# ImageProc2_ver_24e.net
KiCad netlist of a schematic drawn in EAGLE
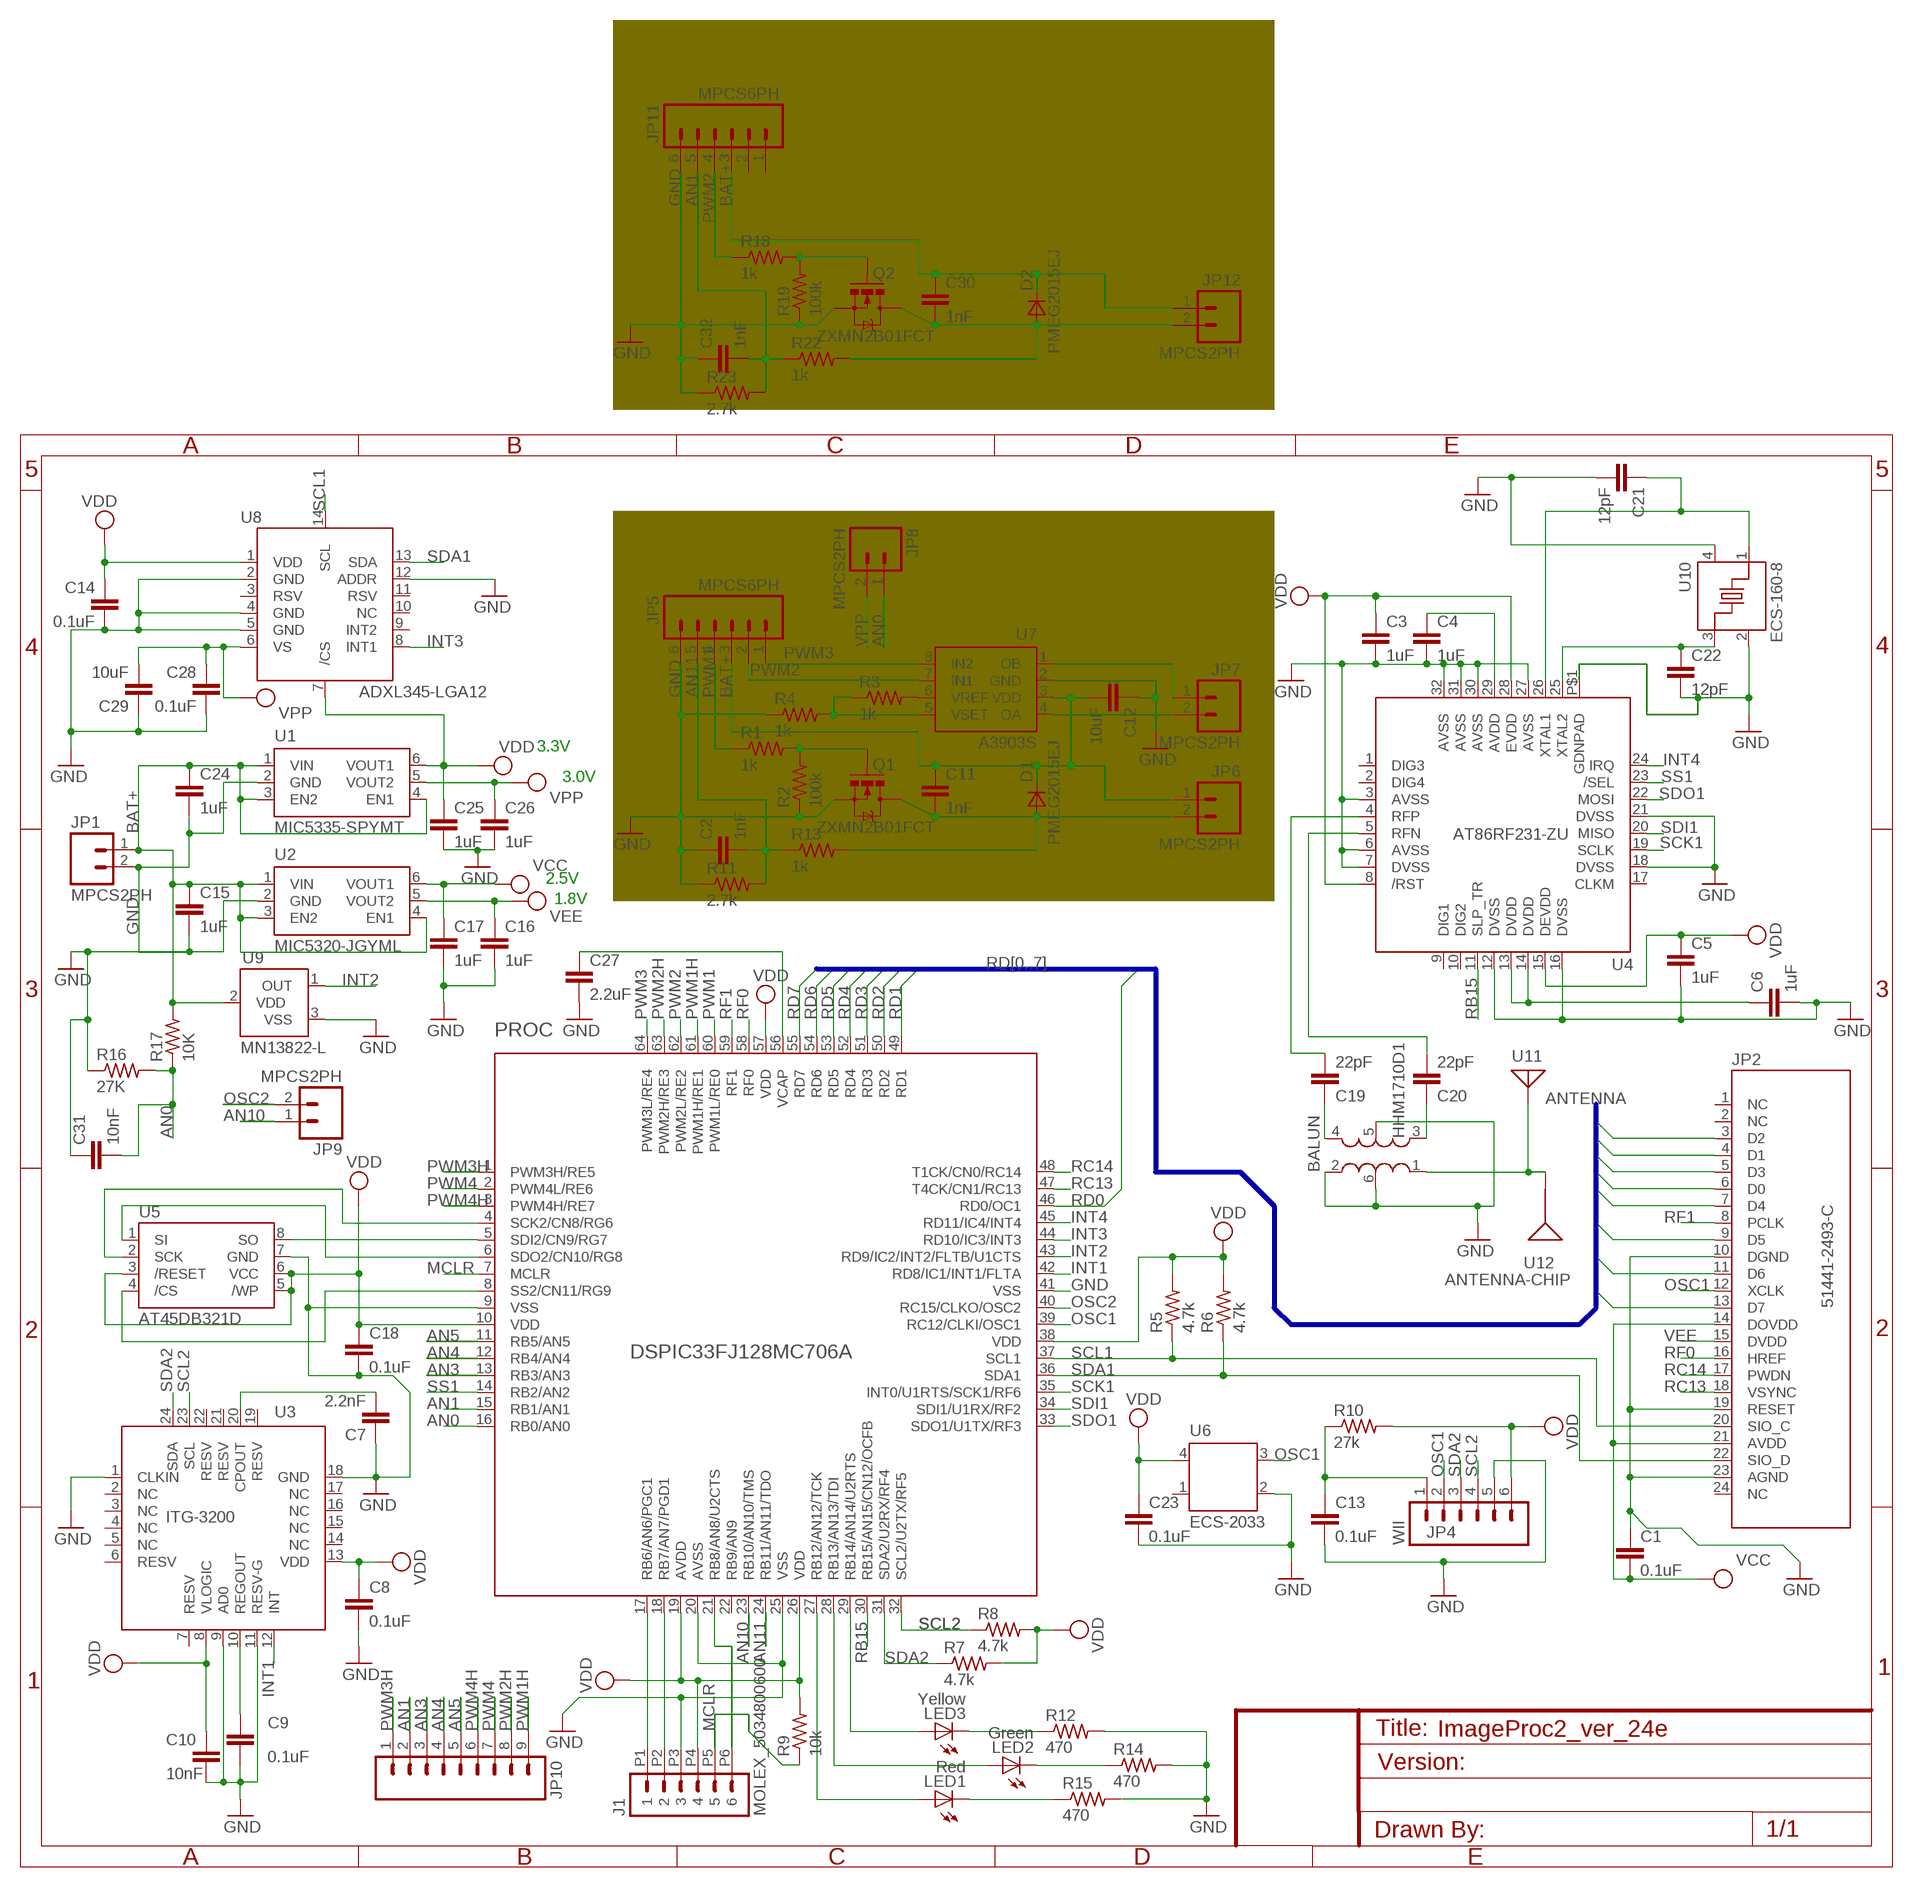
[diagram p0: schematic, sheet 1]

(export (version "E")
  (design (tool "Eeschema 10.0.6"))
  (components
    (comp (ref "BALUN")
      (value "HHM1710D1")
      (footprint "eagle-import:BALUN")
      (libsource (lib "eagle-import") (part "BALUNA"))
    )
    (comp (ref "C1")
      (value "0.1uF")
      (footprint "eagle-import:0402-CAP")
      (libsource (lib "eagle-import") (part "CAP0402-CAP"))
    )
    (comp (ref "C2")
      (value "1nF")
      (footprint "eagle-import:0402-CAP")
      (libsource (lib "eagle-import") (part "CAP0402-CAP"))
    )
    (comp (ref "C3")
      (value "1uF")
      (footprint "eagle-import:0402-CAP")
      (libsource (lib "eagle-import") (part "CAP0402-CAP"))
    )
    (comp (ref "C4")
      (value "1uF")
      (footprint "eagle-import:0402-CAP")
      (libsource (lib "eagle-import") (part "CAP0402-CAP"))
    )
    (comp (ref "C5")
      (value "1uF")
      (footprint "eagle-import:0402-CAP")
      (libsource (lib "eagle-import") (part "CAP0402-CAP"))
    )
    (comp (ref "C6")
      (value "1uF")
      (footprint "eagle-import:0402-CAP")
      (libsource (lib "eagle-import") (part "CAP0402-CAP"))
    )
    (comp (ref "C7")
      (value "2.2nF")
      (footprint "eagle-import:0402-CAP")
      (libsource (lib "eagle-import") (part "CAP0402-CAP"))
    )
    (comp (ref "C8")
      (value "0.1uF")
      (footprint "eagle-import:0402-CAP")
      (libsource (lib "eagle-import") (part "CAP0402-CAP"))
    )
    (comp (ref "C9")
      (value "0.1uF")
      (footprint "eagle-import:0402-CAP")
      (libsource (lib "eagle-import") (part "CAP0402-CAP"))
    )
    (comp (ref "C10")
      (value "10nF")
      (footprint "eagle-import:0402-CAP")
      (libsource (lib "eagle-import") (part "CAP0402-CAP"))
    )
    (comp (ref "C11")
      (value "1nF")
      (footprint "eagle-import:0402-CAP")
      (libsource (lib "eagle-import") (part "CAP0402-CAP"))
    )
    (comp (ref "C12")
      (value "10uF")
      (footprint "eagle-import:0603-CAP")
      (libsource (lib "eagle-import") (part "CAP0603-CAP"))
    )
    (comp (ref "C13")
      (value "0.1uF")
      (footprint "eagle-import:0402-CAP")
      (libsource (lib "eagle-import") (part "CAP0402-CAP"))
    )
    (comp (ref "C14")
      (value "0.1uF")
      (footprint "eagle-import:0402-CAP")
      (libsource (lib "eagle-import") (part "CAP0402-CAP"))
    )
    (comp (ref "C15")
      (value "1uF")
      (footprint "eagle-import:0402-CAP")
      (libsource (lib "eagle-import") (part "CAP0402-CAP"))
    )
    (comp (ref "C16")
      (value "1uF")
      (footprint "eagle-import:0402-CAP")
      (libsource (lib "eagle-import") (part "CAP0402-CAP"))
    )
    (comp (ref "C17")
      (value "1uF")
      (footprint "eagle-import:0402-CAP")
      (libsource (lib "eagle-import") (part "CAP0402-CAP"))
    )
    (comp (ref "C18")
      (value "0.1uF")
      (footprint "eagle-import:0402-CAP")
      (libsource (lib "eagle-import") (part "CAP0402-CAP"))
    )
    (comp (ref "C19")
      (value "22pF")
      (footprint "eagle-import:0402-CAP")
      (libsource (lib "eagle-import") (part "CAP0402-CAP"))
    )
    (comp (ref "C20")
      (value "22pF")
      (footprint "eagle-import:0402-CAP")
      (libsource (lib "eagle-import") (part "CAP0402-CAP"))
    )
    (comp (ref "C21")
      (value "12pF")
      (footprint "eagle-import:0402-CAP")
      (libsource (lib "eagle-import") (part "CAP0402-CAP"))
    )
    (comp (ref "C22")
      (value "12pF")
      (footprint "eagle-import:0402-CAP")
      (libsource (lib "eagle-import") (part "CAP0402-CAP"))
    )
    (comp (ref "C23")
      (value "0.1uF")
      (footprint "eagle-import:0402-CAP")
      (libsource (lib "eagle-import") (part "CAP0402-CAP"))
    )
    (comp (ref "C24")
      (value "1uF")
      (footprint "eagle-import:0402-CAP")
      (libsource (lib "eagle-import") (part "CAP0402-CAP"))
    )
    (comp (ref "C25")
      (value "1uF")
      (footprint "eagle-import:0402-CAP")
      (libsource (lib "eagle-import") (part "CAP0402-CAP"))
    )
    (comp (ref "C26")
      (value "1uF")
      (footprint "eagle-import:0402-CAP")
      (libsource (lib "eagle-import") (part "CAP0402-CAP"))
    )
    (comp (ref "C27")
      (value "2.2uF")
      (footprint "eagle-import:0402-CAP")
      (libsource (lib "eagle-import") (part "CAP0402-CAP"))
    )
    (comp (ref "C28")
      (value "0.1uF")
      (footprint "eagle-import:0402-CAP")
      (libsource (lib "eagle-import") (part "CAP0402-CAP"))
    )
    (comp (ref "C29")
      (value "10uF")
      (footprint "eagle-import:0603-CAP")
      (libsource (lib "eagle-import") (part "CAP0603-CAP"))
    )
    (comp (ref "C30")
      (value "1nF")
      (footprint "eagle-import:0402-CAP")
      (libsource (lib "eagle-import") (part "CAP0402-CAP"))
    )
    (comp (ref "C31")
      (value "10nF")
      (footprint "eagle-import:0402-CAP")
      (libsource (lib "eagle-import") (part "CAP0402-CAP"))
    )
    (comp (ref "C32")
      (value "1nF")
      (footprint "eagle-import:0402-CAP")
      (libsource (lib "eagle-import") (part "CAP0402-CAP"))
    )
    (comp (ref "D1")
      (value "PMEG2015EJ")
      (footprint "eagle-import:SOD323")
      (libsource (lib "eagle-import") (part "DSOD323"))
    )
    (comp (ref "D2")
      (value "PMEG2015EJ")
      (footprint "eagle-import:SOD323")
      (libsource (lib "eagle-import") (part "DSOD323"))
    )
    (comp (ref "J1")
      (value "MOLEX_5034800600")
      (footprint "eagle-import:MOLEX_5034800600")
      (libsource (lib "eagle-import") (part "MOLEX_5034800600"))
    )
    (comp (ref "JP1")
      (value "MPCS2PH")
      (footprint "eagle-import:MOLEX-PICO_CLASP_S2P")
      (libsource (lib "eagle-import") (part "MPCS2PH"))
    )
    (comp (ref "JP2")
      (value "51441-2493-C")
      (footprint "eagle-import:MOLEX-52740-2490")
      (libsource (lib "eagle-import") (part "OV7660FSL_CON-24"))
    )
    (comp (ref "JP4")
      (value "WII")
      (footprint "eagle-import:MOLEX-PICO_CLASP_S6P")
      (libsource (lib "eagle-import") (part "MPCS6PH"))
    )
    (comp (ref "JP5")
      (value "MPCS6PH")
      (footprint "eagle-import:MOLEX-PICO_CLASP_S6P")
      (libsource (lib "eagle-import") (part "MPCS6PH"))
    )
    (comp (ref "JP6")
      (value "MPCS2PH")
      (footprint "eagle-import:MOLEX-PICO_CLASP_S2P")
      (libsource (lib "eagle-import") (part "MPCS2PH"))
    )
    (comp (ref "JP7")
      (value "MPCS2PH")
      (footprint "eagle-import:MOLEX-PICO_CLASP_S2P")
      (libsource (lib "eagle-import") (part "MPCS2PH"))
    )
    (comp (ref "JP8")
      (value "MPCS2PH")
      (footprint "eagle-import:MOLEX-PICO_CLASP_S2P")
      (libsource (lib "eagle-import") (part "MPCS2PH"))
    )
    (comp (ref "JP9")
      (value "MPCS2PH")
      (footprint "eagle-import:MOLEX-PICO_CLASP_S2P")
      (libsource (lib "eagle-import") (part "MPCS2PH"))
    )
    (comp (ref "JP10")
      (value "SOLDER_PADS_9P")
      (footprint "eagle-import:SOLDER_PADS_9P")
      (libsource (lib "eagle-import") (part "SOLDER_PADS_9P"))
    )
    (comp (ref "JP11")
      (value "MPCS6PH")
      (footprint "eagle-import:MOLEX-PICO_CLASP_S6P")
      (libsource (lib "eagle-import") (part "MPCS6PH"))
    )
    (comp (ref "JP12")
      (value "MPCS2PH")
      (footprint "eagle-import:MOLEX-PICO_CLASP_S2P")
      (libsource (lib "eagle-import") (part "MPCS2PH"))
    )
    (comp (ref "LED1")
      (value "Red")
      (footprint "eagle-import:CHIP-LED0603")
      (libsource (lib "eagle-import") (part "LEDCHIP-LED0603"))
    )
    (comp (ref "LED2")
      (value "Green")
      (footprint "eagle-import:CHIP-LED0603")
      (libsource (lib "eagle-import") (part "LEDCHIP-LED0603"))
    )
    (comp (ref "LED3")
      (value "Yellow")
      (footprint "eagle-import:CHIP-LED0603")
      (libsource (lib "eagle-import") (part "LEDCHIP-LED0603"))
    )
    (comp (ref "PROC")
      (value "DSPIC33FJ128MC706A")
      (footprint "eagle-import:TQFP64")
      (libsource (lib "eagle-import") (part "DSPIC33FJ128MC706-I/PT"))
    )
    (comp (ref "Q1")
      (value "ZXMN2B01FCT")
      (footprint "eagle-import:SOT23-3")
      (libsource (lib "eagle-import") (part "MOSFET-NCHANNELSMD"))
    )
    (comp (ref "Q2")
      (value "ZXMN2B01FCT")
      (footprint "eagle-import:SOT23-3")
      (libsource (lib "eagle-import") (part "MOSFET-NCHANNELSMD"))
    )
    (comp (ref "R1")
      (value "1k")
      (footprint "eagle-import:R0402")
      (libsource (lib "eagle-import") (part "R-US_R0402"))
    )
    (comp (ref "R2")
      (value "100k")
      (footprint "eagle-import:R0402")
      (libsource (lib "eagle-import") (part "R-US_R0402"))
    )
    (comp (ref "R3")
      (value "1k")
      (footprint "eagle-import:R0402")
      (libsource (lib "eagle-import") (part "R-US_R0402"))
    )
    (comp (ref "R4")
      (value "1k")
      (footprint "eagle-import:R0402")
      (libsource (lib "eagle-import") (part "R-US_R0402"))
    )
    (comp (ref "R5")
      (value "4.7k")
      (footprint "eagle-import:R0402")
      (libsource (lib "eagle-import") (part "R-US_R0402"))
    )
    (comp (ref "R6")
      (value "4.7k")
      (footprint "eagle-import:R0402")
      (libsource (lib "eagle-import") (part "R-US_R0402"))
    )
    (comp (ref "R7")
      (value "4.7k")
      (footprint "eagle-import:R0402")
      (libsource (lib "eagle-import") (part "R-US_R0402"))
    )
    (comp (ref "R8")
      (value "4.7k")
      (footprint "eagle-import:R0402")
      (libsource (lib "eagle-import") (part "R-US_R0402"))
    )
    (comp (ref "R9")
      (value "10k")
      (footprint "eagle-import:R0402")
      (libsource (lib "eagle-import") (part "R-US_R0402"))
    )
    (comp (ref "R10")
      (value "27k")
      (footprint "eagle-import:R0402")
      (libsource (lib "eagle-import") (part "R-US_R0402"))
    )
    (comp (ref "R11")
      (value "2.7k")
      (footprint "eagle-import:R0402")
      (libsource (lib "eagle-import") (part "R-US_R0402"))
    )
    (comp (ref "R12")
      (value "470")
      (footprint "eagle-import:R0402")
      (libsource (lib "eagle-import") (part "R-US_R0402"))
    )
    (comp (ref "R13")
      (value "1k")
      (footprint "eagle-import:R0402")
      (libsource (lib "eagle-import") (part "R-US_R0402"))
    )
    (comp (ref "R14")
      (value "470")
      (footprint "eagle-import:R0402")
      (libsource (lib "eagle-import") (part "R-US_R0402"))
    )
    (comp (ref "R15")
      (value "470")
      (footprint "eagle-import:R0402")
      (libsource (lib "eagle-import") (part "R-US_R0402"))
    )
    (comp (ref "R16")
      (value "27K")
      (footprint "eagle-import:R0402")
      (libsource (lib "eagle-import") (part "R-US_R0402"))
    )
    (comp (ref "R17")
      (value "10K")
      (footprint "eagle-import:R0402")
      (libsource (lib "eagle-import") (part "R-US_R0402"))
    )
    (comp (ref "R18")
      (value "1k")
      (footprint "eagle-import:R0402")
      (libsource (lib "eagle-import") (part "R-US_R0402"))
    )
    (comp (ref "R19")
      (value "100k")
      (footprint "eagle-import:R0402")
      (libsource (lib "eagle-import") (part "R-US_R0402"))
    )
    (comp (ref "R22")
      (value "1k")
      (footprint "eagle-import:R0402")
      (libsource (lib "eagle-import") (part "R-US_R0402"))
    )
    (comp (ref "R23")
      (value "2.7k")
      (footprint "eagle-import:R0402")
      (libsource (lib "eagle-import") (part "R-US_R0402"))
    )
    (comp (ref "U1")
      (value "MIC5335-SPYMT")
      (footprint "eagle-import:MLF-6")
      (libsource (lib "eagle-import") (part "MIC5320-JGYML"))
    )
    (comp (ref "U2")
      (value "MIC5320-JGYML")
      (footprint "eagle-import:MLF-6")
      (libsource (lib "eagle-import") (part "MIC5320-JGYML"))
    )
    (comp (ref "U3")
      (value "ITG-3200")
      (footprint "eagle-import:QFN-24")
      (libsource (lib "eagle-import") (part "ITG-3200-00"))
    )
    (comp (ref "U4")
      (value "AT86RF231-ZU")
      (footprint "eagle-import:QFN-32")
      (libsource (lib "eagle-import") (part "AT86RF231-ZU"))
    )
    (comp (ref "U5")
      (value "AT45DB321D")
      (footprint "eagle-import:MLF(VDFN)-8")
      (libsource (lib "eagle-import") (part "AT45DB321D"))
    )
    (comp (ref "U6")
      (value "ECS-2033")
      (footprint "eagle-import:OSCILLATOR-SMD")
      (libsource (lib "eagle-import") (part "OSCILLATORS"))
    )
    (comp (ref "U7")
      (value "A3903S")
      (footprint "eagle-import:DFN-8")
      (libsource (lib "eagle-import") (part "A3903S"))
    )
    (comp (ref "U8")
      (value "ADXL345-LGA12")
      (footprint "eagle-import:LGA14")
      (libsource (lib "eagle-import") (part "ADXL345"))
    )
    (comp (ref "U9")
      (value "MN13822-L")
      (footprint "eagle-import:SOT-23-3")
      (libsource (lib "eagle-import") (part "VOL_DETECTOR"))
    )
    (comp (ref "U10")
      (value "ECS-160-8")
      (footprint "eagle-import:CRYSTAL-SMD")
      (libsource (lib "eagle-import") (part "CRYSTALS"))
    )
    (comp (ref "U11")
      (value "ANTENNA")
      (footprint "eagle-import:ANTENNA_PAD")
      (libsource (lib "eagle-import") (part "ANTENNA"))
    )
    (comp (ref "U12")
      (value "ANTENNA-CHIP")
      (footprint "eagle-import:ANTENNA-CHIP")
      (libsource (lib "eagle-import") (part "ANTENNA-CHIP"))
    )
  )
  (nets
    (net (code "1") (name "/AN0") (class "Default")
      (node (ref "C31") (pin "2") (pinfunction "2_2") (pintype "passive"))
      (node (ref "JP8") (pin "1") (pinfunction "1_1") (pintype "passive"))
      (node (ref "PROC") (pin "16") (pinfunction "RB0/AN0_16") (pintype "bidirectional"))
      (node (ref "R16") (pin "2") (pinfunction "2_2") (pintype "passive"))
      (node (ref "R17") (pin "1") (pinfunction "1_1") (pintype "passive"))
    )
    (net (code "2") (name "/AN1") (class "Default")
      (node (ref "C32") (pin "2") (pinfunction "2_2") (pintype "passive"))
      (node (ref "JP10") (pin "2") (pinfunction "2_2") (pintype "passive"))
      (node (ref "JP11") (pin "5") (pinfunction "5_5") (pintype "passive"))
      (node (ref "PROC") (pin "15") (pinfunction "RB1/AN1_15") (pintype "bidirectional"))
      (node (ref "R22") (pin "1") (pinfunction "1_1") (pintype "passive"))
      (node (ref "R23") (pin "2") (pinfunction "2_2") (pintype "passive"))
    )
    (net (code "3") (name "/AN3") (class "Default")
      (node (ref "JP10") (pin "3") (pinfunction "3_3") (pintype "passive"))
      (node (ref "PROC") (pin "13") (pinfunction "RB3/AN3_13") (pintype "bidirectional"))
    )
    (net (code "4") (name "/AN4") (class "Default")
      (node (ref "JP10") (pin "4") (pinfunction "4_4") (pintype "passive"))
      (node (ref "PROC") (pin "12") (pinfunction "RB4/AN4_12") (pintype "bidirectional"))
    )
    (net (code "5") (name "/AN5") (class "Default")
      (node (ref "JP10") (pin "5") (pinfunction "5_5") (pintype "passive"))
      (node (ref "PROC") (pin "11") (pinfunction "RB5/AN5_11") (pintype "bidirectional"))
    )
    (net (code "6") (name "/AN10") (class "Default")
      (node (ref "JP9") (pin "1") (pinfunction "1_1") (pintype "passive"))
      (node (ref "PROC") (pin "23") (pinfunction "RB10/AN10/TMS_23") (pintype "bidirectional"))
    )
    (net (code "7") (name "/AN11") (class "Default")
      (node (ref "C2") (pin "2") (pinfunction "2_2") (pintype "passive"))
      (node (ref "JP5") (pin "5") (pinfunction "5_5") (pintype "passive"))
      (node (ref "PROC") (pin "24") (pinfunction "RB11/AN11/TDO_24") (pintype "bidirectional"))
      (node (ref "R11") (pin "2") (pinfunction "2_2") (pintype "passive"))
      (node (ref "R13") (pin "1") (pinfunction "1_1") (pintype "passive"))
    )
    (net (code "8") (name "/BAT+") (class "Default")
      (node (ref "C11") (pin "1") (pinfunction "1_1") (pintype "passive"))
      (node (ref "C12") (pin "2") (pinfunction "2_2") (pintype "passive"))
      (node (ref "C15") (pin "1") (pinfunction "1_1") (pintype "passive"))
      (node (ref "C24") (pin "1") (pinfunction "1_1") (pintype "passive"))
      (node (ref "C30") (pin "1") (pinfunction "1_1") (pintype "passive"))
      (node (ref "D1") (pin "1") (pinfunction "C_1") (pintype "passive"))
      (node (ref "D2") (pin "1") (pinfunction "C_1") (pintype "passive"))
      (node (ref "JP1") (pin "1") (pinfunction "1_1") (pintype "passive"))
      (node (ref "JP11") (pin "3") (pinfunction "3_3") (pintype "passive"))
      (node (ref "JP12") (pin "1") (pinfunction "1_1") (pintype "passive"))
      (node (ref "JP5") (pin "3") (pinfunction "3_3") (pintype "passive"))
      (node (ref "JP6") (pin "1") (pinfunction "1_1") (pintype "passive"))
      (node (ref "R17") (pin "2") (pinfunction "2_2") (pintype "passive"))
      (node (ref "U1") (pin "1") (pinfunction "VIN_1") (pintype "bidirectional"))
      (node (ref "U1") (pin "3") (pinfunction "EN2_3") (pintype "bidirectional"))
      (node (ref "U1") (pin "4") (pinfunction "EN1_4") (pintype "bidirectional"))
      (node (ref "U2") (pin "1") (pinfunction "VIN_1") (pintype "bidirectional"))
      (node (ref "U2") (pin "3") (pinfunction "EN2_3") (pintype "bidirectional"))
      (node (ref "U2") (pin "4") (pinfunction "EN1_4") (pintype "bidirectional"))
      (node (ref "U7") (pin "3") (pinfunction "VDD_3") (pintype "bidirectional"))
      (node (ref "U9") (pin "2") (pinfunction "VDD_2") (pintype "bidirectional"))
    )
    (net (code "9") (name "/INT1") (class "Default")
      (node (ref "PROC") (pin "42") (pinfunction "RD8/IC1/INT1/FLTA_42") (pintype "bidirectional"))
      (node (ref "U3") (pin "12") (pinfunction "INT_12") (pintype "bidirectional"))
    )
    (net (code "10") (name "/INT2") (class "Default")
      (node (ref "PROC") (pin "43") (pinfunction "RD9/IC2/INT2/FLTB/U1CTS_43") (pintype "bidirectional"))
      (node (ref "U9") (pin "1") (pinfunction "OUT_1") (pintype "bidirectional"))
    )
    (net (code "11") (name "/INT3") (class "Default")
      (node (ref "PROC") (pin "44") (pinfunction "RD10/IC3/INT3_44") (pintype "bidirectional"))
      (node (ref "U8") (pin "8") (pinfunction "INT1_8") (pintype "bidirectional"))
    )
    (net (code "12") (name "/INT4") (class "Default")
      (node (ref "PROC") (pin "45") (pinfunction "RD11/IC4/INT4_45") (pintype "bidirectional"))
      (node (ref "U4") (pin "24") (pinfunction "IRQ_24") (pintype "bidirectional"))
    )
    (net (code "13") (name "/MCLR") (class "Default")
      (node (ref "J1") (pin "P5") (pinfunction "5_P5") (pintype "passive"))
      (node (ref "PROC") (pin "7") (pinfunction "MCLR_7") (pintype "input"))
      (node (ref "R9") (pin "1") (pinfunction "1_1") (pintype "passive"))
    )
    (net (code "14") (name "/OSC1") (class "Default")
      (node (ref "JP2") (pin "12") (pinfunction "XCLK_12") (pintype "bidirectional"))
      (node (ref "JP4") (pin "2") (pinfunction "2_2") (pintype "passive"))
      (node (ref "PROC") (pin "39") (pinfunction "RC12/CLKI/OSC1_39") (pintype "bidirectional"))
      (node (ref "U6") (pin "3") (pinfunction "OUT_3") (pintype "bidirectional"))
    )
    (net (code "15") (name "/OSC2") (class "Default")
      (node (ref "JP9") (pin "2") (pinfunction "2_2") (pintype "passive"))
      (node (ref "PROC") (pin "40") (pinfunction "RC15/CLKO/OSC2_40") (pintype "bidirectional"))
    )
    (net (code "16") (name "/PWM1") (class "Default")
      (node (ref "JP5") (pin "4") (pinfunction "4_4") (pintype "passive"))
      (node (ref "PROC") (pin "60") (pinfunction "PWM1L/RE0_60") (pintype "bidirectional"))
      (node (ref "R1") (pin "1") (pinfunction "1_1") (pintype "passive"))
    )
    (net (code "17") (name "/PWM1H") (class "Default")
      (node (ref "JP10") (pin "9") (pinfunction "9_9") (pintype "passive"))
      (node (ref "PROC") (pin "61") (pinfunction "PWM1H/RE1_61") (pintype "bidirectional"))
    )
    (net (code "18") (name "/PWM2") (class "Default")
      (node (ref "JP11") (pin "4") (pinfunction "4_4") (pintype "passive"))
      (node (ref "JP5") (pin "2") (pinfunction "2_2") (pintype "passive"))
      (node (ref "PROC") (pin "62") (pinfunction "PWM2L/RE2_62") (pintype "bidirectional"))
      (node (ref "R18") (pin "1") (pinfunction "1_1") (pintype "passive"))
      (node (ref "U7") (pin "7") (pinfunction "IN1_7") (pintype "bidirectional"))
    )
    (net (code "19") (name "/PWM2H") (class "Default")
      (node (ref "JP10") (pin "8") (pinfunction "8_8") (pintype "passive"))
      (node (ref "PROC") (pin "63") (pinfunction "PWM2H/RE3_63") (pintype "bidirectional"))
    )
    (net (code "20") (name "/PWM3") (class "Default")
      (node (ref "JP5") (pin "1") (pinfunction "1_1") (pintype "passive"))
      (node (ref "PROC") (pin "64") (pinfunction "PWM3L/RE4_64") (pintype "bidirectional"))
      (node (ref "U7") (pin "8") (pinfunction "IN2_8") (pintype "bidirectional"))
    )
    (net (code "21") (name "/PWM3H") (class "Default")
      (node (ref "JP10") (pin "1") (pinfunction "1_1") (pintype "passive"))
      (node (ref "PROC") (pin "1") (pinfunction "PWM3H/RE5_1") (pintype "bidirectional"))
    )
    (net (code "22") (name "/PWM4") (class "Default")
      (node (ref "JP10") (pin "7") (pinfunction "7_7") (pintype "passive"))
      (node (ref "PROC") (pin "2") (pinfunction "PWM4L/RE6_2") (pintype "bidirectional"))
    )
    (net (code "23") (name "/PWM4H") (class "Default")
      (node (ref "JP10") (pin "6") (pinfunction "6_6") (pintype "passive"))
      (node (ref "PROC") (pin "3") (pinfunction "PWM4H/RE7_3") (pintype "bidirectional"))
    )
    (net (code "24") (name "/RB15") (class "Default")
      (node (ref "PROC") (pin "30") (pinfunction "RB15/AN15/CN12/OCFB_30") (pintype "bidirectional"))
      (node (ref "U4") (pin "11") (pinfunction "SLP_TR_11") (pintype "bidirectional"))
    )
    (net (code "25") (name "/RC13") (class "Default")
      (node (ref "JP2") (pin "18") (pinfunction "VSYNC_18") (pintype "bidirectional"))
      (node (ref "PROC") (pin "47") (pinfunction "T4CK/CN1/RC13_47") (pintype "bidirectional"))
    )
    (net (code "26") (name "/RC14") (class "Default")
      (node (ref "JP2") (pin "17") (pinfunction "PWDN_17") (pintype "bidirectional"))
      (node (ref "PROC") (pin "48") (pinfunction "T1CK/CN0/RC14_48") (pintype "bidirectional"))
    )
    (net (code "27") (name "/RD0") (class "Default")
      (node (ref "JP2") (pin "6") (pinfunction "D0_6") (pintype "bidirectional"))
      (node (ref "PROC") (pin "46") (pinfunction "RD0/OC1_46") (pintype "bidirectional"))
    )
    (net (code "28") (name "/RD1") (class "Default")
      (node (ref "JP2") (pin "4") (pinfunction "D1_4") (pintype "bidirectional"))
      (node (ref "PROC") (pin "49") (pinfunction "RD1_49") (pintype "bidirectional"))
    )
    (net (code "29") (name "/RD2") (class "Default")
      (node (ref "JP2") (pin "3") (pinfunction "D2_3") (pintype "bidirectional"))
      (node (ref "PROC") (pin "50") (pinfunction "RD2_50") (pintype "bidirectional"))
    )
    (net (code "30") (name "/RD3") (class "Default")
      (node (ref "JP2") (pin "5") (pinfunction "D3_5") (pintype "bidirectional"))
      (node (ref "PROC") (pin "51") (pinfunction "RD3_51") (pintype "bidirectional"))
    )
    (net (code "31") (name "/RD4") (class "Default")
      (node (ref "JP2") (pin "7") (pinfunction "D4_7") (pintype "bidirectional"))
      (node (ref "PROC") (pin "52") (pinfunction "RD4_52") (pintype "bidirectional"))
    )
    (net (code "32") (name "/RD5") (class "Default")
      (node (ref "JP2") (pin "9") (pinfunction "D5_9") (pintype "bidirectional"))
      (node (ref "PROC") (pin "53") (pinfunction "RD5_53") (pintype "bidirectional"))
    )
    (net (code "33") (name "/RD6") (class "Default")
      (node (ref "JP2") (pin "11") (pinfunction "D6_11") (pintype "bidirectional"))
      (node (ref "PROC") (pin "54") (pinfunction "RD6_54") (pintype "bidirectional"))
    )
    (net (code "34") (name "/RD7") (class "Default")
      (node (ref "JP2") (pin "13") (pinfunction "D7_13") (pintype "bidirectional"))
      (node (ref "PROC") (pin "55") (pinfunction "RD7_55") (pintype "bidirectional"))
    )
    (net (code "36") (name "/RF0") (class "Default")
      (node (ref "JP2") (pin "16") (pinfunction "HREF_16") (pintype "bidirectional"))
      (node (ref "PROC") (pin "58") (pinfunction "RF0_58") (pintype "bidirectional"))
    )
    (net (code "37") (name "/RF1") (class "Default")
      (node (ref "JP2") (pin "8") (pinfunction "PCLK_8") (pintype "bidirectional"))
      (node (ref "PROC") (pin "59") (pinfunction "RF1_59") (pintype "bidirectional"))
    )
    (net (code "38") (name "/SCK1") (class "Default")
      (node (ref "PROC") (pin "35") (pinfunction "INT0/U1RTS/SCK1/RF6_35") (pintype "bidirectional"))
      (node (ref "U4") (pin "19") (pinfunction "SCLK_19") (pintype "bidirectional"))
    )
    (net (code "39") (name "/SCL1") (class "Default")
      (node (ref "JP2") (pin "20") (pinfunction "SIO_C_20") (pintype "bidirectional"))
      (node (ref "PROC") (pin "37") (pinfunction "SCL1_37") (pintype "bidirectional"))
      (node (ref "R5") (pin "1") (pinfunction "1_1") (pintype "passive"))
      (node (ref "U8") (pin "14") (pinfunction "SCL_14") (pintype "bidirectional"))
    )
    (net (code "40") (name "/SCL2") (class "Default")
      (node (ref "JP4") (pin "4") (pinfunction "4_4") (pintype "passive"))
      (node (ref "PROC") (pin "32") (pinfunction "SCL2/U2TX/RF5_32") (pintype "bidirectional"))
      (node (ref "R8") (pin "1") (pinfunction "1_1") (pintype "passive"))
      (node (ref "U3") (pin "23") (pinfunction "SCL_23") (pintype "bidirectional"))
    )
    (net (code "41") (name "/SDA1") (class "Default")
      (node (ref "JP2") (pin "22") (pinfunction "SIO_D_22") (pintype "bidirectional"))
      (node (ref "PROC") (pin "36") (pinfunction "SDA1_36") (pintype "bidirectional"))
      (node (ref "R6") (pin "1") (pinfunction "1_1") (pintype "passive"))
      (node (ref "U8") (pin "13") (pinfunction "SDA_13") (pintype "bidirectional"))
    )
    (net (code "42") (name "/SDA2") (class "Default")
      (node (ref "JP4") (pin "3") (pinfunction "3_3") (pintype "passive"))
      (node (ref "PROC") (pin "31") (pinfunction "SDA2/U2RX/RF4_31") (pintype "bidirectional"))
      (node (ref "R7") (pin "1") (pinfunction "1_1") (pintype "passive"))
      (node (ref "U3") (pin "24") (pinfunction "SDA_24") (pintype "bidirectional"))
    )
    (net (code "43") (name "/SDI1") (class "Default")
      (node (ref "PROC") (pin "34") (pinfunction "SDI1/U1RX/RF2_34") (pintype "bidirectional"))
      (node (ref "U4") (pin "20") (pinfunction "MISO_20") (pintype "bidirectional"))
    )
    (net (code "44") (name "/SDO1") (class "Default")
      (node (ref "PROC") (pin "33") (pinfunction "SDO1/U1TX/RF3_33") (pintype "bidirectional"))
      (node (ref "U4") (pin "22") (pinfunction "MOSI_22") (pintype "bidirectional"))
    )
    (net (code "45") (name "/SS1") (class "Default")
      (node (ref "PROC") (pin "14") (pinfunction "RB2/AN2_14") (pintype "bidirectional"))
      (node (ref "U4") (pin "23") (pinfunction "/SEL_23") (pintype "bidirectional"))
    )
    (net (code "46") (name "GND") (class "Default")
      (node (ref "BALUN") (pin "2") (pinfunction "RFGND_2") (pintype "bidirectional"))
      (node (ref "BALUN") (pin "5") (pinfunction "GND_5") (pintype "bidirectional"))
      (node (ref "BALUN") (pin "6") (pinfunction "NC_6") (pintype "bidirectional"))
      (node (ref "C1") (pin "1") (pinfunction "1_1") (pintype "passive"))
      (node (ref "C10") (pin "2") (pinfunction "2_2") (pintype "passive"))
      (node (ref "C12") (pin "1") (pinfunction "1_1") (pintype "passive"))
      (node (ref "C13") (pin "2") (pinfunction "2_2") (pintype "passive"))
      (node (ref "C14") (pin "2") (pinfunction "2_2") (pintype "passive"))
      (node (ref "C15") (pin "2") (pinfunction "2_2") (pintype "passive"))
      (node (ref "C16") (pin "2") (pinfunction "2_2") (pintype "passive"))
      (node (ref "C17") (pin "2") (pinfunction "2_2") (pintype "passive"))
      (node (ref "C18") (pin "2") (pinfunction "2_2") (pintype "passive"))
      (node (ref "C2") (pin "1") (pinfunction "1_1") (pintype "passive"))
      (node (ref "C21") (pin "2") (pinfunction "2_2") (pintype "passive"))
      (node (ref "C22") (pin "2") (pinfunction "2_2") (pintype "passive"))
      (node (ref "C23") (pin "2") (pinfunction "2_2") (pintype "passive"))
      (node (ref "C24") (pin "2") (pinfunction "2_2") (pintype "passive"))
      (node (ref "C25") (pin "2") (pinfunction "2_2") (pintype "passive"))
      (node (ref "C26") (pin "2") (pinfunction "2_2") (pintype "passive"))
      (node (ref "C27") (pin "2") (pinfunction "2_2") (pintype "passive"))
      (node (ref "C28") (pin "2") (pinfunction "2_2") (pintype "passive"))
      (node (ref "C29") (pin "1") (pinfunction "1_1") (pintype "passive"))
      (node (ref "C3") (pin "2") (pinfunction "2_2") (pintype "passive"))
      (node (ref "C31") (pin "1") (pinfunction "1_1") (pintype "passive"))
      (node (ref "C32") (pin "1") (pinfunction "1_1") (pintype "passive"))
      (node (ref "C4") (pin "2") (pinfunction "2_2") (pintype "passive"))
      (node (ref "C5") (pin "2") (pinfunction "2_2") (pintype "passive"))
      (node (ref "C6") (pin "2") (pinfunction "2_2") (pintype "passive"))
      (node (ref "C7") (pin "1") (pinfunction "1_1") (pintype "passive"))
      (node (ref "C8") (pin "2") (pinfunction "2_2") (pintype "passive"))
      (node (ref "C9") (pin "2") (pinfunction "2_2") (pintype "passive"))
      (node (ref "J1") (pin "P3") (pinfunction "3_P3") (pintype "passive"))
      (node (ref "JP1") (pin "2") (pinfunction "2_2") (pintype "passive"))
      (node (ref "JP11") (pin "6") (pinfunction "6_6") (pintype "passive"))
      (node (ref "JP2") (pin "10") (pinfunction "DGND_10") (pintype "bidirectional"))
      (node (ref "JP2") (pin "19") (pinfunction "RESET_19") (pintype "bidirectional"))
      (node (ref "JP2") (pin "23") (pinfunction "AGND_23") (pintype "bidirectional"))
      (node (ref "JP4") (pin "5") (pinfunction "5_5") (pintype "passive"))
      (node (ref "JP5") (pin "6") (pinfunction "6_6") (pintype "passive"))
      (node (ref "PROC") (pin "20") (pinfunction "AVSS_20") (pintype "power_in"))
      (node (ref "PROC") (pin "25") (pinfunction "VSS_25") (pintype "power_in"))
      (node (ref "PROC") (pin "41") (pinfunction "VSS_41") (pintype "power_in"))
      (node (ref "PROC") (pin "9") (pinfunction "VSS_9") (pintype "power_in"))
      (node (ref "Q1") (pin "2") (pinfunction "S_2") (pintype "passive"))
      (node (ref "Q2") (pin "2") (pinfunction "S_2") (pintype "passive"))
      (node (ref "R11") (pin "1") (pinfunction "1_1") (pintype "passive"))
      (node (ref "R12") (pin "2") (pinfunction "2_2") (pintype "passive"))
      (node (ref "R14") (pin "2") (pinfunction "2_2") (pintype "passive"))
      (node (ref "R15") (pin "2") (pinfunction "2_2") (pintype "passive"))
      (node (ref "R16") (pin "1") (pinfunction "1_1") (pintype "passive"))
      (node (ref "R19") (pin "1") (pinfunction "1_1") (pintype "passive"))
      (node (ref "R2") (pin "1") (pinfunction "1_1") (pintype "passive"))
      (node (ref "R23") (pin "1") (pinfunction "1_1") (pintype "passive"))
      (node (ref "R4") (pin "1") (pinfunction "1_1") (pintype "passive"))
      (node (ref "U1") (pin "2") (pinfunction "GND_2") (pintype "bidirectional"))
      (node (ref "U10") (pin "2") (pinfunction "GND_2") (pintype "bidirectional"))
      (node (ref "U10") (pin "4") (pinfunction "GND_4") (pintype "bidirectional"))
      (node (ref "U2") (pin "2") (pinfunction "GND_2") (pintype "bidirectional"))
      (node (ref "U3") (pin "1") (pinfunction "CLKIN_1") (pintype "bidirectional"))
      (node (ref "U3") (pin "11") (pinfunction "RESV-G_11") (pintype "bidirectional"))
      (node (ref "U3") (pin "18") (pinfunction "GND_18") (pintype "bidirectional"))
      (node (ref "U3") (pin "9") (pinfunction "AD0_9") (pintype "bidirectional"))
      (node (ref "U4") (pin "12") (pinfunction "DVSS_12") (pintype "bidirectional"))
      (node (ref "U4") (pin "16") (pinfunction "DVSS_16") (pintype "bidirectional"))
      (node (ref "U4") (pin "18") (pinfunction "DVSS_18") (pintype "bidirectional"))
      (node (ref "U4") (pin "21") (pinfunction "DVSS_21") (pintype "bidirectional"))
      (node (ref "U4") (pin "27") (pinfunction "AVSS_27") (pintype "bidirectional"))
      (node (ref "U4") (pin "3") (pinfunction "AVSS_3") (pintype "bidirectional"))
      (node (ref "U4") (pin "30") (pinfunction "AVSS_30") (pintype "bidirectional"))
      (node (ref "U4") (pin "31") (pinfunction "AVSS_31") (pintype "bidirectional"))
      (node (ref "U4") (pin "32") (pinfunction "AVSS_32") (pintype "bidirectional"))
      (node (ref "U4") (pin "6") (pinfunction "AVSS_6") (pintype "bidirectional"))
      (node (ref "U4") (pin "7") (pinfunction "DVSS_7") (pintype "bidirectional"))
      (node (ref "U4") (pin "P$1") (pinfunction "GDNPAD_P$1") (pintype "bidirectional"))
      (node (ref "U5") (pin "7") (pinfunction "GND_7") (pintype "bidirectional"))
      (node (ref "U6") (pin "2") (pinfunction "GND_2") (pintype "bidirectional"))
      (node (ref "U7") (pin "2") (pinfunction "GND_2") (pintype "bidirectional"))
      (node (ref "U8") (pin "12") (pinfunction "ADDR_12") (pintype "bidirectional"))
      (node (ref "U8") (pin "2") (pinfunction "GND_2") (pintype "bidirectional"))
      (node (ref "U8") (pin "4") (pinfunction "GND_4") (pintype "bidirectional"))
      (node (ref "U8") (pin "5") (pinfunction "GND_5") (pintype "bidirectional"))
      (node (ref "U9") (pin "3") (pinfunction "VSS_3") (pintype "bidirectional"))
    )
    (net (code "47") (name "Net-(BALUN-BAL3)") (class "Default")
      (node (ref "BALUN") (pin "3") (pinfunction "BAL3_3") (pintype "bidirectional"))
      (node (ref "C20") (pin "1") (pinfunction "1_1") (pintype "passive"))
    )
    (net (code "48") (name "Net-(BALUN-BAL4)") (class "Default")
      (node (ref "BALUN") (pin "4") (pinfunction "BAL4_4") (pintype "bidirectional"))
      (node (ref "C19") (pin "1") (pinfunction "1_1") (pintype "passive"))
    )
    (net (code "49") (name "Net-(BALUN-UNBAL)") (class "Default")
      (node (ref "BALUN") (pin "1") (pinfunction "UNBAL_1") (pintype "bidirectional"))
      (node (ref "U11") (pin "P$1") (pinfunction "1_P$1") (pintype "output"))
      (node (ref "U12") (pin "SIG") (pinfunction "SIGNAL_SIG") (pintype "bidirectional"))
    )
    (net (code "50") (name "Net-(C6-Pad1)") (class "Default")
      (node (ref "C6") (pin "1") (pinfunction "1_1") (pintype "passive"))
      (node (ref "U4") (pin "13") (pinfunction "DVDD_13") (pintype "bidirectional"))
      (node (ref "U4") (pin "14") (pinfunction "DVDD_14") (pintype "bidirectional"))
    )
    (net (code "51") (name "Net-(C13-Pad1)") (class "Default")
      (node (ref "C13") (pin "1") (pinfunction "1_1") (pintype "passive"))
      (node (ref "JP4") (pin "1") (pinfunction "1_1") (pintype "passive"))
      (node (ref "R10") (pin "1") (pinfunction "1_1") (pintype "passive"))
    )
    (net (code "52") (name "Net-(D1-A)") (class "Default")
      (node (ref "C11") (pin "2") (pinfunction "2_2") (pintype "passive"))
      (node (ref "D1") (pin "2") (pinfunction "A_2") (pintype "passive"))
      (node (ref "JP6") (pin "2") (pinfunction "2_2") (pintype "passive"))
      (node (ref "Q1") (pin "3") (pinfunction "D_3") (pintype "passive"))
      (node (ref "R13") (pin "2") (pinfunction "2_2") (pintype "passive"))
    )
    (net (code "53") (name "Net-(D2-A)") (class "Default")
      (node (ref "C30") (pin "2") (pinfunction "2_2") (pintype "passive"))
      (node (ref "D2") (pin "2") (pinfunction "A_2") (pintype "passive"))
      (node (ref "JP12") (pin "2") (pinfunction "2_2") (pintype "passive"))
      (node (ref "Q2") (pin "3") (pinfunction "D_3") (pintype "passive"))
      (node (ref "R22") (pin "2") (pinfunction "2_2") (pintype "passive"))
    )
    (net (code "54") (name "Net-(J1-1)") (class "Default")
      (node (ref "J1") (pin "P1") (pinfunction "1_P1") (pintype "passive"))
      (node (ref "PROC") (pin "17") (pinfunction "RB6/AN6/PGC1_17") (pintype "bidirectional"))
    )
    (net (code "55") (name "Net-(J1-2)") (class "Default")
      (node (ref "J1") (pin "P2") (pinfunction "2_P2") (pintype "passive"))
      (node (ref "PROC") (pin "18") (pinfunction "RB7/AN7/PGD1_18") (pintype "bidirectional"))
    )
    (net (code "56") (name "Net-(J1-6)") (class "Default")
      (node (ref "J1") (pin "P6") (pinfunction "6_P6") (pintype "passive"))
      (node (ref "PROC") (pin "21") (pinfunction "RB8/AN8/U2CTS_21") (pintype "bidirectional"))
    )
    (net (code "57") (name "Net-(LED1-PadC)") (class "Default")
      (node (ref "LED1") (pin "C") (pinfunction "C_C") (pintype "passive"))
      (node (ref "R15") (pin "1") (pinfunction "1_1") (pintype "passive"))
    )
    (net (code "58") (name "Net-(LED2-PadC)") (class "Default")
      (node (ref "LED2") (pin "C") (pinfunction "C_C") (pintype "passive"))
      (node (ref "R14") (pin "1") (pinfunction "1_1") (pintype "passive"))
    )
    (net (code "59") (name "Net-(LED3-PadC)") (class "Default")
      (node (ref "LED3") (pin "C") (pinfunction "C_C") (pintype "passive"))
      (node (ref "R12") (pin "1") (pinfunction "1_1") (pintype "passive"))
    )
    (net (code "60") (name "Net-(PROC-RB12{slash}AN12{slash}TCK)") (class "Default")
      (node (ref "LED1") (pin "A") (pinfunction "A_A") (pintype "passive"))
      (node (ref "PROC") (pin "27") (pinfunction "RB12/AN12/TCK_27") (pintype "bidirectional"))
    )
    (net (code "61") (name "Net-(PROC-RB13{slash}AN13{slash}TDI)") (class "Default")
      (node (ref "LED2") (pin "A") (pinfunction "A_A") (pintype "passive"))
      (node (ref "PROC") (pin "28") (pinfunction "RB13/AN13/TDI_28") (pintype "bidirectional"))
    )
    (net (code "62") (name "Net-(PROC-RB14{slash}AN14{slash}U2RTS)") (class "Default")
      (node (ref "LED3") (pin "A") (pinfunction "A_A") (pintype "passive"))
      (node (ref "PROC") (pin "29") (pinfunction "RB14/AN14/U2RTS_29") (pintype "bidirectional"))
    )
    (net (code "63") (name "Net-(PROC-SCK2{slash}CN8{slash}RG6)") (class "Default")
      (node (ref "PROC") (pin "4") (pinfunction "SCK2/CN8/RG6_4") (pintype "bidirectional"))
      (node (ref "U5") (pin "2") (pinfunction "SCK_2") (pintype "bidirectional"))
    )
    (net (code "64") (name "Net-(PROC-SDI2{slash}CN9{slash}RG7)") (class "Default")
      (node (ref "PROC") (pin "5") (pinfunction "SDI2/CN9/RG7_5") (pintype "bidirectional"))
      (node (ref "U5") (pin "8") (pinfunction "SO_8") (pintype "bidirectional"))
    )
    (net (code "65") (name "Net-(PROC-SDO2{slash}CN10{slash}RG8)") (class "Default")
      (node (ref "PROC") (pin "6") (pinfunction "SDO2/CN10/RG8_6") (pintype "bidirectional"))
      (node (ref "U5") (pin "1") (pinfunction "SI_1") (pintype "bidirectional"))
    )
    (net (code "66") (name "Net-(PROC-SS2{slash}CN11{slash}RG9)") (class "Default")
      (node (ref "PROC") (pin "8") (pinfunction "SS2/CN11/RG9_8") (pintype "bidirectional"))
      (node (ref "U5") (pin "4") (pinfunction "/CS_4") (pintype "bidirectional"))
    )
    (net (code "67") (name "Net-(PROC-VCAP)") (class "Default")
      (node (ref "C27") (pin "1") (pinfunction "1_1") (pintype "passive"))
      (node (ref "PROC") (pin "56") (pinfunction "VCAP_56") (pintype "power_in"))
    )
    (net (code "68") (name "Net-(Q1-G)") (class "Default")
      (node (ref "Q1") (pin "1") (pinfunction "G_1") (pintype "passive"))
      (node (ref "R1") (pin "2") (pinfunction "2_2") (pintype "passive"))
      (node (ref "R2") (pin "2") (pinfunction "2_2") (pintype "passive"))
    )
    (net (code "69") (name "Net-(Q2-G)") (class "Default")
      (node (ref "Q2") (pin "1") (pinfunction "G_1") (pintype "passive"))
      (node (ref "R18") (pin "2") (pinfunction "2_2") (pintype "passive"))
      (node (ref "R19") (pin "2") (pinfunction "2_2") (pintype "passive"))
    )
    (net (code "70") (name "Net-(U3-CPOUT)") (class "Default")
      (node (ref "C7") (pin "2") (pinfunction "2_2") (pintype "passive"))
      (node (ref "U3") (pin "20") (pinfunction "CPOUT_20") (pintype "bidirectional"))
    )
    (net (code "71") (name "Net-(U3-REGOUT)") (class "Default")
      (node (ref "C9") (pin "1") (pinfunction "1_1") (pintype "passive"))
      (node (ref "U3") (pin "10") (pinfunction "REGOUT_10") (pintype "bidirectional"))
    )
    (net (code "72") (name "Net-(U4-AVDD)") (class "Default")
      (node (ref "C4") (pin "1") (pinfunction "1_1") (pintype "passive"))
      (node (ref "U4") (pin "29") (pinfunction "AVDD_29") (pintype "bidirectional"))
    )
    (net (code "73") (name "Net-(U4-RFN)") (class "Default")
      (node (ref "C20") (pin "2") (pinfunction "2_2") (pintype "passive"))
      (node (ref "U4") (pin "5") (pinfunction "RFN_5") (pintype "bidirectional"))
    )
    (net (code "74") (name "Net-(U4-RFP)") (class "Default")
      (node (ref "C19") (pin "2") (pinfunction "2_2") (pintype "passive"))
      (node (ref "U4") (pin "4") (pinfunction "RFP_4") (pintype "bidirectional"))
    )
    (net (code "75") (name "Net-(U4-XTAL1)") (class "Default")
      (node (ref "C21") (pin "1") (pinfunction "1_1") (pintype "passive"))
      (node (ref "U10") (pin "1") (pinfunction "IN/OUT_1") (pintype "bidirectional"))
      (node (ref "U4") (pin "26") (pinfunction "XTAL1_26") (pintype "bidirectional"))
    )
    (net (code "76") (name "Net-(U4-XTAL2)") (class "Default")
      (node (ref "C22") (pin "1") (pinfunction "1_1") (pintype "passive"))
      (node (ref "U10") (pin "3") (pinfunction "IN/OUT_3") (pintype "bidirectional"))
      (node (ref "U4") (pin "25") (pinfunction "XTAL2_25") (pintype "bidirectional"))
    )
    (net (code "77") (name "Net-(U7-OA)") (class "Default")
      (node (ref "JP7") (pin "2") (pinfunction "2_2") (pintype "passive"))
      (node (ref "U7") (pin "4") (pinfunction "OA_4") (pintype "bidirectional"))
    )
    (net (code "78") (name "Net-(U7-OB)") (class "Default")
      (node (ref "JP7") (pin "1") (pinfunction "1_1") (pintype "passive"))
      (node (ref "U7") (pin "1") (pinfunction "OB_1") (pintype "bidirectional"))
    )
    (net (code "79") (name "Net-(U7-VREF)") (class "Default")
      (node (ref "R3") (pin "2") (pinfunction "2_2") (pintype "passive"))
      (node (ref "U7") (pin "6") (pinfunction "VREF_6") (pintype "bidirectional"))
    )
    (net (code "80") (name "Net-(U7-VSET)") (class "Default")
      (node (ref "R3") (pin "1") (pinfunction "1_1") (pintype "passive"))
      (node (ref "R4") (pin "2") (pinfunction "2_2") (pintype "passive"))
      (node (ref "U7") (pin "5") (pinfunction "VSET_5") (pintype "bidirectional"))
    )
    (net (code "81") (name "VCC") (class "Default")
      (node (ref "C1") (pin "2") (pinfunction "2_2") (pintype "passive"))
      (node (ref "C17") (pin "1") (pinfunction "1_1") (pintype "passive"))
      (node (ref "JP2") (pin "14") (pinfunction "DOVDD_14") (pintype "bidirectional"))
      (node (ref "JP2") (pin "21") (pinfunction "AVDD_21") (pintype "bidirectional"))
      (node (ref "U2") (pin "6") (pinfunction "VOUT1_6") (pintype "bidirectional"))
    )
    (net (code "82") (name "VDD") (class "Default")
      (node (ref "C10") (pin "1") (pinfunction "1_1") (pintype "passive"))
      (node (ref "C14") (pin "1") (pinfunction "1_1") (pintype "passive"))
      (node (ref "C18") (pin "1") (pinfunction "1_1") (pintype "passive"))
      (node (ref "C23") (pin "1") (pinfunction "1_1") (pintype "passive"))
      (node (ref "C25") (pin "1") (pinfunction "1_1") (pintype "passive"))
      (node (ref "C3") (pin "1") (pinfunction "1_1") (pintype "passive"))
      (node (ref "C5") (pin "1") (pinfunction "1_1") (pintype "passive"))
      (node (ref "C8") (pin "1") (pinfunction "1_1") (pintype "passive"))
      (node (ref "J1") (pin "P4") (pinfunction "4_P4") (pintype "passive"))
      (node (ref "JP4") (pin "6") (pinfunction "6_6") (pintype "passive"))
      (node (ref "PROC") (pin "10") (pinfunction "VDD_10") (pintype "power_in"))
      (node (ref "PROC") (pin "19") (pinfunction "AVDD_19") (pintype "power_in"))
      (node (ref "PROC") (pin "26") (pinfunction "VDD_26") (pintype "power_in"))
      (node (ref "PROC") (pin "38") (pinfunction "VDD_38") (pintype "power_in"))
      (node (ref "PROC") (pin "57") (pinfunction "VDD_57") (pintype "power_in"))
      (node (ref "R10") (pin "2") (pinfunction "2_2") (pintype "passive"))
      (node (ref "R5") (pin "2") (pinfunction "2_2") (pintype "passive"))
      (node (ref "R6") (pin "2") (pinfunction "2_2") (pintype "passive"))
      (node (ref "R7") (pin "2") (pinfunction "2_2") (pintype "passive"))
      (node (ref "R8") (pin "2") (pinfunction "2_2") (pintype "passive"))
      (node (ref "R9") (pin "2") (pinfunction "2_2") (pintype "passive"))
      (node (ref "U1") (pin "6") (pinfunction "VOUT1_6") (pintype "bidirectional"))
      (node (ref "U3") (pin "13") (pinfunction "VDD_13") (pintype "bidirectional"))
      (node (ref "U3") (pin "8") (pinfunction "VLOGIC_8") (pintype "bidirectional"))
      (node (ref "U4") (pin "15") (pinfunction "DEVDD_15") (pintype "bidirectional"))
      (node (ref "U4") (pin "28") (pinfunction "EVDD_28") (pintype "bidirectional"))
      (node (ref "U4") (pin "8") (pinfunction "/RST_8") (pintype "bidirectional"))
      (node (ref "U5") (pin "3") (pinfunction "/RESET_3") (pintype "bidirectional"))
      (node (ref "U5") (pin "5") (pinfunction "/WP_5") (pintype "bidirectional"))
      (node (ref "U5") (pin "6") (pinfunction "VCC_6") (pintype "bidirectional"))
      (node (ref "U6") (pin "4") (pinfunction "VDD_4") (pintype "bidirectional"))
      (node (ref "U8") (pin "1") (pinfunction "VDD_1") (pintype "bidirectional"))
      (node (ref "U8") (pin "7") (pinfunction "/CS_7") (pintype "bidirectional"))
    )
    (net (code "83") (name "VEE") (class "Default")
      (node (ref "C16") (pin "1") (pinfunction "1_1") (pintype "passive"))
      (node (ref "JP2") (pin "15") (pinfunction "DVDD_15") (pintype "bidirectional"))
      (node (ref "U2") (pin "5") (pinfunction "VOUT2_5") (pintype "bidirectional"))
    )
    (net (code "84") (name "VPP") (class "Default")
      (node (ref "C26") (pin "1") (pinfunction "1_1") (pintype "passive"))
      (node (ref "C28") (pin "1") (pinfunction "1_1") (pintype "passive"))
      (node (ref "C29") (pin "2") (pinfunction "2_2") (pintype "passive"))
      (node (ref "JP8") (pin "2") (pinfunction "2_2") (pintype "passive"))
      (node (ref "U1") (pin "5") (pinfunction "VOUT2_5") (pintype "bidirectional"))
      (node (ref "U8") (pin "6") (pinfunction "VS_6") (pintype "bidirectional"))
    )
    (net (code "85") (name "unconnected-(JP2-NC-Pad1)") (class "Default")
      (node (ref "JP2") (pin "1") (pinfunction "NC_1") (pintype "bidirectional"))
    )
    (net (code "86") (name "unconnected-(JP2-NC-Pad2)") (class "Default")
      (node (ref "JP2") (pin "2") (pinfunction "NC_2") (pintype "bidirectional"))
    )
    (net (code "87") (name "unconnected-(JP2-NC-Pad24)") (class "Default")
      (node (ref "JP2") (pin "24") (pinfunction "NC_24") (pintype "bidirectional"))
    )
    (net (code "88") (name "unconnected-(JP11-Pad1)") (class "Default")
      (node (ref "JP11") (pin "1") (pinfunction "1_1") (pintype "passive"))
    )
    (net (code "89") (name "unconnected-(JP11-Pad2)") (class "Default")
      (node (ref "JP11") (pin "2") (pinfunction "2_2") (pintype "passive"))
    )
    (net (code "90") (name "unconnected-(PROC-RB9{slash}AN9-Pad22)") (class "Default")
      (node (ref "PROC") (pin "22") (pinfunction "RB9/AN9_22") (pintype "bidirectional"))
    )
    (net (code "91") (name "unconnected-(U3-NC-Pad2)") (class "Default")
      (node (ref "U3") (pin "2") (pinfunction "NC_2") (pintype "bidirectional"))
    )
    (net (code "92") (name "unconnected-(U3-NC-Pad3)") (class "Default")
      (node (ref "U3") (pin "3") (pinfunction "NC_3") (pintype "bidirectional"))
    )
    (net (code "93") (name "unconnected-(U3-NC-Pad4)") (class "Default")
      (node (ref "U3") (pin "4") (pinfunction "NC_4") (pintype "bidirectional"))
    )
    (net (code "94") (name "unconnected-(U3-NC-Pad5)") (class "Default")
      (node (ref "U3") (pin "5") (pinfunction "NC_5") (pintype "bidirectional"))
    )
    (net (code "95") (name "unconnected-(U3-NC-Pad14)") (class "Default")
      (node (ref "U3") (pin "14") (pinfunction "NC_14") (pintype "bidirectional"))
    )
    (net (code "96") (name "unconnected-(U3-NC-Pad15)") (class "Default")
      (node (ref "U3") (pin "15") (pinfunction "NC_15") (pintype "bidirectional"))
    )
    (net (code "97") (name "unconnected-(U3-NC-Pad16)") (class "Default")
      (node (ref "U3") (pin "16") (pinfunction "NC_16") (pintype "bidirectional"))
    )
    (net (code "98") (name "unconnected-(U3-NC-Pad17)") (class "Default")
      (node (ref "U3") (pin "17") (pinfunction "NC_17") (pintype "bidirectional"))
    )
    (net (code "99") (name "unconnected-(U3-RESV-Pad6)") (class "Default")
      (node (ref "U3") (pin "6") (pinfunction "RESV_6") (pintype "bidirectional"))
    )
    (net (code "100") (name "unconnected-(U3-RESV-Pad7)") (class "Default")
      (node (ref "U3") (pin "7") (pinfunction "RESV_7") (pintype "bidirectional"))
    )
    (net (code "101") (name "unconnected-(U3-RESV-Pad19)") (class "Default")
      (node (ref "U3") (pin "19") (pinfunction "RESV_19") (pintype "bidirectional"))
    )
    (net (code "102") (name "unconnected-(U3-RESV-Pad21)") (class "Default")
      (node (ref "U3") (pin "21") (pinfunction "RESV_21") (pintype "bidirectional"))
    )
    (net (code "103") (name "unconnected-(U3-RESV-Pad22)") (class "Default")
      (node (ref "U3") (pin "22") (pinfunction "RESV_22") (pintype "bidirectional"))
    )
    (net (code "104") (name "unconnected-(U4-CLKM-Pad17)") (class "Default")
      (node (ref "U4") (pin "17") (pinfunction "CLKM_17") (pintype "bidirectional"))
    )
    (net (code "105") (name "unconnected-(U4-DIG1-Pad9)") (class "Default")
      (node (ref "U4") (pin "9") (pinfunction "DIG1_9") (pintype "bidirectional"))
    )
    (net (code "106") (name "unconnected-(U4-DIG2-Pad10)") (class "Default")
      (node (ref "U4") (pin "10") (pinfunction "DIG2_10") (pintype "bidirectional"))
    )
    (net (code "107") (name "unconnected-(U4-DIG3-Pad1)") (class "Default")
      (node (ref "U4") (pin "1") (pinfunction "DIG3_1") (pintype "bidirectional"))
    )
    (net (code "108") (name "unconnected-(U4-DIG4-Pad2)") (class "Default")
      (node (ref "U4") (pin "2") (pinfunction "DIG4_2") (pintype "bidirectional"))
    )
    (net (code "109") (name "unconnected-(U6-NC-Pad1)") (class "Default")
      (node (ref "U6") (pin "1") (pinfunction "NC_1") (pintype "bidirectional"))
    )
    (net (code "110") (name "unconnected-(U8-INT2-Pad9)") (class "Default")
      (node (ref "U8") (pin "9") (pinfunction "INT2_9") (pintype "bidirectional"))
    )
    (net (code "111") (name "unconnected-(U8-NC-Pad10)") (class "Default")
      (node (ref "U8") (pin "10") (pinfunction "NC_10") (pintype "bidirectional"))
    )
    (net (code "112") (name "unconnected-(U8-RSV-Pad3)") (class "Default")
      (node (ref "U8") (pin "3") (pinfunction "RSV_3") (pintype "bidirectional"))
    )
    (net (code "113") (name "unconnected-(U8-RSV-Pad11)") (class "Default")
      (node (ref "U8") (pin "11") (pinfunction "RSV_11") (pintype "bidirectional"))
    )
  )
)
